# EFR32BG24_PartC.net
KiCad netlist of a schematic drawn in Altium Designer
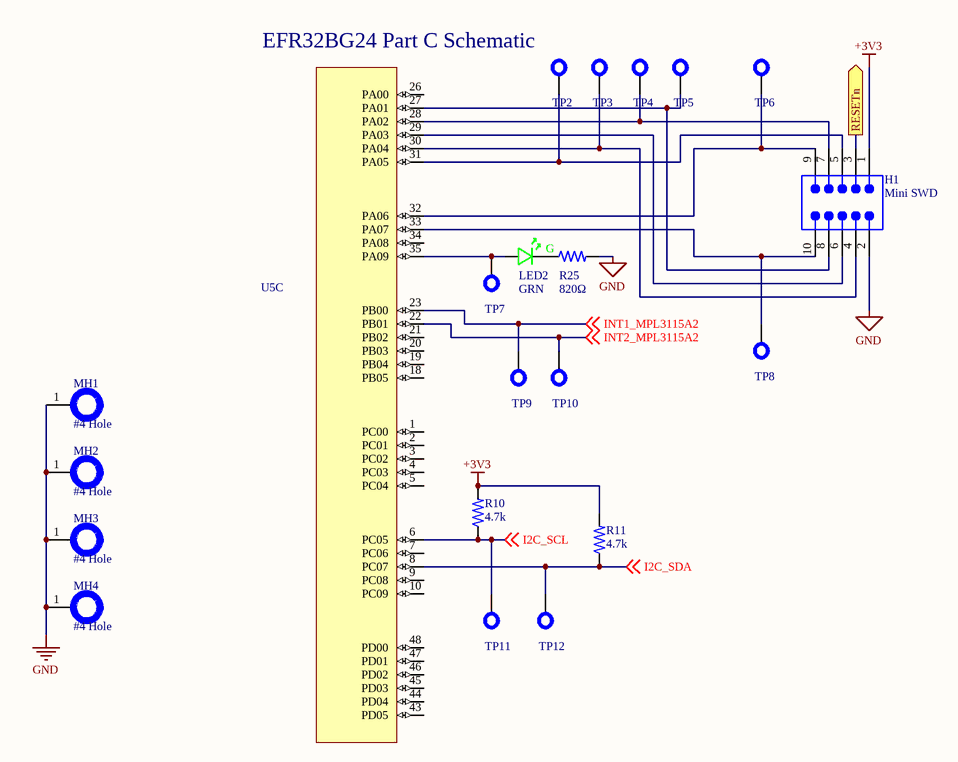
[diagram p0: EFR32BG24_PartC.SchDoc]

(export (version "E")
  (design (tool "Eeschema 10.0.6"))
  (components
    (comp (ref "H1")
      (value "Mini SWD")
      (footprint "FTSH-105-01-XXX-DV-K")
      (description "Mini SWD 0.05\" Pitch Connector - 10 Pin SMT Box Header")
      (fields
        (field (name "MANUFACTURER") "Adafruit Industries")
        (field (name "MANUFACTURER PART NUMBER") "4048")
      )
      (libsource (lib "Connectors") (part "Debug Connector Mini SWD - 0.05{dblquote}"))
    )
    (comp (ref "LED2")
      (value "GRN")
      (footprint "LED_0603")
      (description "LED, 0603, GREEN, 430MCD, 520NM")
      (fields
        (field (name "MANUFACTURER") "Wurth Electronics")
        (field (name "MANUFACTURER PART NUMBER") "150060GS75000")
      )
      (libsource (lib "LPEDT_Parts") (part "LED_GREEN_0603"))
    )
    (comp (ref "MH1")
      (value "#4 Hole")
      (footprint "HOLE_#4")
      (libsource (lib "LPEDT_Parts") (part "HOLE_#4"))
    )
    (comp (ref "MH2")
      (value "#4 Hole")
      (footprint "HOLE_#4")
      (libsource (lib "LPEDT_Parts") (part "HOLE_#4"))
    )
    (comp (ref "MH3")
      (value "#4 Hole")
      (footprint "HOLE_#4")
      (libsource (lib "LPEDT_Parts") (part "HOLE_#4"))
    )
    (comp (ref "MH4")
      (value "#4 Hole")
      (footprint "HOLE_#4")
      (libsource (lib "LPEDT_Parts") (part "HOLE_#4"))
    )
    (comp (ref "R10")
      (value "4.7k")
      (footprint "R_0603")
      (fields
        (field (name "MANUFACTURER") "Yageo")
        (field (name "MANUFACTURER PART NUMBER") "RC0603FR-074K7L")
        (field (name "TOLERANCE") "1%")
      )
      (libsource (lib "LPEDT_Parts") (part "R_4K7_0603"))
    )
    (comp (ref "R11")
      (value "4.7k")
      (footprint "R_0603")
      (fields
        (field (name "MANUFACTURER") "Yageo")
        (field (name "MANUFACTURER PART NUMBER") "RC0603FR-074K7L")
        (field (name "TOLERANCE") "1%")
      )
      (libsource (lib "LPEDT_Parts") (part "R_4K7_0603"))
    )
    (comp (ref "R25")
      (value "820Ω")
      (footprint "R_0603")
      (description "RES 820OHM 0.1W 0603")
      (fields
        (field (name "MANUFACTURER") "Stackpole Electronics")
        (field (name "MANUFACTURER PART NUMBER") "RMCF0603FT820R")
      )
      (libsource (lib "LPEDT_Parts") (part "R_820_0603"))
    )
    (comp (ref "TP2")
      (value "TP_1PIN_Hole")
      (footprint "Test Point")
      (description "200 mil hole test point")
      (libsource (lib "LPEDT_Parts") (part "TP_1PIN_Hole"))
    )
    (comp (ref "TP3")
      (value "TP_1PIN_Hole")
      (footprint "Test Point")
      (description "200 mil hole test point")
      (libsource (lib "LPEDT_Parts") (part "TP_1PIN_Hole"))
    )
    (comp (ref "TP4")
      (value "TP_1PIN_Hole")
      (footprint "Test Point")
      (description "200 mil hole test point")
      (libsource (lib "LPEDT_Parts") (part "TP_1PIN_Hole"))
    )
    (comp (ref "TP5")
      (value "TP_1PIN_Hole")
      (footprint "Test Point")
      (description "200 mil hole test point")
      (libsource (lib "LPEDT_Parts") (part "TP_1PIN_Hole"))
    )
    (comp (ref "TP6")
      (value "TP_1PIN_Hole")
      (footprint "Test Point")
      (description "200 mil hole test point")
      (libsource (lib "LPEDT_Parts") (part "TP_1PIN_Hole"))
    )
    (comp (ref "TP7")
      (value "TP_1PIN_Hole")
      (footprint "Test Point")
      (description "200 mil hole test point")
      (libsource (lib "LPEDT_Parts") (part "TP_1PIN_Hole"))
    )
    (comp (ref "TP8")
      (value "TP_1PIN_Hole")
      (footprint "Test Point")
      (description "200 mil hole test point")
      (libsource (lib "LPEDT_Parts") (part "TP_1PIN_Hole"))
    )
    (comp (ref "TP9")
      (value "TP_1PIN_Hole")
      (footprint "Test Point")
      (description "200 mil hole test point")
      (libsource (lib "LPEDT_Parts") (part "TP_1PIN_Hole"))
    )
    (comp (ref "TP10")
      (value "TP_1PIN_Hole")
      (footprint "Test Point")
      (description "200 mil hole test point")
      (libsource (lib "LPEDT_Parts") (part "TP_1PIN_Hole"))
    )
    (comp (ref "TP11")
      (value "TP_1PIN_Hole")
      (footprint "Test Point")
      (description "200 mil hole test point")
      (libsource (lib "LPEDT_Parts") (part "TP_1PIN_Hole"))
    )
    (comp (ref "TP12")
      (value "TP_1PIN_Hole")
      (footprint "Test Point")
      (description "200 mil hole test point")
      (libsource (lib "LPEDT_Parts") (part "TP_1PIN_Hole"))
    )
    (comp (ref "U5")
      (value "EFR32BG24B110F1536IM48-B")
      (footprint "U_48QFN_6x6_2")
      (description "BG24, 2.4 GHz, 1536kB Flash, 256kB RAM, +10 dBm, Secure Vault High, 20-bit ADC +125C, QFN48")
      (fields (field (name "MANUFACTURER") "Silicon Labs"))
      (libsource (lib "LPEDT_Parts") (part "EFR32BG24B110F1536IM48-B"))
    )
  )
  (nets
    (net (code "1") (name "+3V3") (class "Default")
      (node (ref "H1") (pin "1") (pinfunction "1_1") (pintype "passive"))
      (node (ref "R10") (pin "2") (pinfunction "2_2") (pintype "passive"))
      (node (ref "R11") (pin "2") (pinfunction "2_2") (pintype "passive"))
    )
    (net (code "2") (name "/RESETn") (class "Default")
      (node (ref "H1") (pin "3") (pinfunction "3_3") (pintype "passive"))
    )
    (net (code "3") (name "GND") (class "Default")
      (node (ref "H1") (pin "2") (pinfunction "2_2") (pintype "passive"))
      (node (ref "MH1") (pin "1") (pinfunction "1_1") (pintype "passive"))
      (node (ref "MH2") (pin "1") (pinfunction "1_1") (pintype "passive"))
      (node (ref "MH3") (pin "1") (pinfunction "1_1") (pintype "passive"))
      (node (ref "MH4") (pin "1") (pinfunction "1_1") (pintype "passive"))
      (node (ref "R25") (pin "2") (pinfunction "2_2") (pintype "passive"))
    )
    (net (code "4") (name "I2C_SCL") (class "Default")
      (node (ref "R10") (pin "1") (pinfunction "1_1") (pintype "passive"))
      (node (ref "TP11") (pin "1") (pinfunction "1_1") (pintype "passive"))
      (node (ref "U5") (pin "6") (pinfunction "PC05_6") (pintype "bidirectional"))
    )
    (net (code "5") (name "I2C_SDA") (class "Default")
      (node (ref "R11") (pin "1") (pinfunction "1_1") (pintype "passive"))
      (node (ref "TP12") (pin "1") (pinfunction "1_1") (pintype "passive"))
      (node (ref "U5") (pin "8") (pinfunction "PC07_8") (pintype "bidirectional"))
    )
    (net (code "6") (name "INT1_MPL3115A2") (class "Default")
      (node (ref "TP9") (pin "1") (pinfunction "1_1") (pintype "passive"))
      (node (ref "U5") (pin "23") (pinfunction "PB00_23") (pintype "bidirectional"))
    )
    (net (code "7") (name "INT2_MPL3115A2") (class "Default")
      (node (ref "TP10") (pin "1") (pinfunction "1_1") (pintype "passive"))
      (node (ref "U5") (pin "22") (pinfunction "PB01_22") (pintype "bidirectional"))
    )
    (net (code "8") (name "Net-(LED2-PadC)") (class "Default")
      (node (ref "LED2") (pin "C") (pinfunction "C_C") (pintype "passive"))
      (node (ref "R25") (pin "1") (pinfunction "1_1") (pintype "passive"))
    )
    (net (code "9") (name "Net-(U5C-PA01)") (class "Default")
      (node (ref "H1") (pin "8") (pinfunction "8_8") (pintype "passive"))
      (node (ref "TP5") (pin "1") (pinfunction "1_1") (pintype "passive"))
      (node (ref "U5") (pin "27") (pinfunction "PA01_27") (pintype "bidirectional"))
    )
    (net (code "10") (name "Net-(U5C-PA02)") (class "Default")
      (node (ref "H1") (pin "7") (pinfunction "7_7") (pintype "passive"))
      (node (ref "TP4") (pin "1") (pinfunction "1_1") (pintype "passive"))
      (node (ref "U5") (pin "28") (pinfunction "PA02_28") (pintype "bidirectional"))
    )
    (net (code "11") (name "Net-(U5C-PA03)") (class "Default")
      (node (ref "H1") (pin "6") (pinfunction "6_6") (pintype "passive"))
      (node (ref "U5") (pin "29") (pinfunction "PA03_29") (pintype "bidirectional"))
    )
    (net (code "12") (name "Net-(U5C-PA04)") (class "Default")
      (node (ref "H1") (pin "4") (pinfunction "4_4") (pintype "passive"))
      (node (ref "TP3") (pin "1") (pinfunction "1_1") (pintype "passive"))
      (node (ref "U5") (pin "30") (pinfunction "PA04_30") (pintype "bidirectional"))
    )
    (net (code "13") (name "Net-(U5C-PA05)") (class "Default")
      (node (ref "H1") (pin "5") (pinfunction "5_5") (pintype "passive"))
      (node (ref "TP2") (pin "1") (pinfunction "1_1") (pintype "passive"))
      (node (ref "U5") (pin "31") (pinfunction "PA05_31") (pintype "bidirectional"))
    )
    (net (code "14") (name "Net-(U5C-PA06)") (class "Default")
      (node (ref "H1") (pin "9") (pinfunction "9_9") (pintype "passive"))
      (node (ref "TP6") (pin "1") (pinfunction "1_1") (pintype "passive"))
      (node (ref "U5") (pin "32") (pinfunction "PA06_32") (pintype "bidirectional"))
    )
    (net (code "15") (name "Net-(U5C-PA07)") (class "Default")
      (node (ref "H1") (pin "10") (pinfunction "10_10") (pintype "passive"))
      (node (ref "TP8") (pin "1") (pinfunction "1_1") (pintype "passive"))
      (node (ref "U5") (pin "33") (pinfunction "PA07_33") (pintype "bidirectional"))
    )
    (net (code "16") (name "Net-(U5C-PA09)") (class "Default")
      (node (ref "LED2") (pin "A") (pinfunction "A_A") (pintype "passive"))
      (node (ref "TP7") (pin "1") (pinfunction "1_1") (pintype "passive"))
      (node (ref "U5") (pin "35") (pinfunction "PA09_35") (pintype "bidirectional"))
    )
    (net (code "17") (name "unconnected-(U5C-PA00-Pad26)") (class "Default")
      (node (ref "U5") (pin "26") (pinfunction "PA00_26") (pintype "bidirectional"))
    )
    (net (code "18") (name "unconnected-(U5C-PA08-Pad34)") (class "Default")
      (node (ref "U5") (pin "34") (pinfunction "PA08_34") (pintype "bidirectional"))
    )
    (net (code "19") (name "unconnected-(U5C-PB02-Pad21)") (class "Default")
      (node (ref "U5") (pin "21") (pinfunction "PB02_21") (pintype "bidirectional"))
    )
    (net (code "20") (name "unconnected-(U5C-PB03-Pad20)") (class "Default")
      (node (ref "U5") (pin "20") (pinfunction "PB03_20") (pintype "bidirectional"))
    )
    (net (code "21") (name "unconnected-(U5C-PB04-Pad19)") (class "Default")
      (node (ref "U5") (pin "19") (pinfunction "PB04_19") (pintype "bidirectional"))
    )
    (net (code "22") (name "unconnected-(U5C-PB05-Pad18)") (class "Default")
      (node (ref "U5") (pin "18") (pinfunction "PB05_18") (pintype "bidirectional"))
    )
    (net (code "23") (name "unconnected-(U5C-PC00-Pad1)") (class "Default")
      (node (ref "U5") (pin "1") (pinfunction "PC00_1") (pintype "bidirectional"))
    )
    (net (code "24") (name "unconnected-(U5C-PC01-Pad2)") (class "Default")
      (node (ref "U5") (pin "2") (pinfunction "PC01_2") (pintype "bidirectional"))
    )
    (net (code "25") (name "unconnected-(U5C-PC02-Pad3)") (class "Default")
      (node (ref "U5") (pin "3") (pinfunction "PC02_3") (pintype "bidirectional"))
    )
    (net (code "26") (name "unconnected-(U5C-PC03-Pad4)") (class "Default")
      (node (ref "U5") (pin "4") (pinfunction "PC03_4") (pintype "bidirectional"))
    )
    (net (code "27") (name "unconnected-(U5C-PC04-Pad5)") (class "Default")
      (node (ref "U5") (pin "5") (pinfunction "PC04_5") (pintype "bidirectional"))
    )
    (net (code "28") (name "unconnected-(U5C-PC06-Pad7)") (class "Default")
      (node (ref "U5") (pin "7") (pinfunction "PC06_7") (pintype "bidirectional"))
    )
    (net (code "29") (name "unconnected-(U5C-PC08-Pad9)") (class "Default")
      (node (ref "U5") (pin "9") (pinfunction "PC08_9") (pintype "bidirectional"))
    )
    (net (code "30") (name "unconnected-(U5C-PC09-Pad10)") (class "Default")
      (node (ref "U5") (pin "10") (pinfunction "PC09_10") (pintype "bidirectional"))
    )
    (net (code "31") (name "unconnected-(U5C-PD00-Pad48)") (class "Default")
      (node (ref "U5") (pin "48") (pinfunction "PD00_48") (pintype "bidirectional"))
    )
    (net (code "32") (name "unconnected-(U5C-PD01-Pad47)") (class "Default")
      (node (ref "U5") (pin "47") (pinfunction "PD01_47") (pintype "bidirectional"))
    )
    (net (code "33") (name "unconnected-(U5C-PD02-Pad46)") (class "Default")
      (node (ref "U5") (pin "46") (pinfunction "PD02_46") (pintype "bidirectional"))
    )
    (net (code "34") (name "unconnected-(U5C-PD03-Pad45)") (class "Default")
      (node (ref "U5") (pin "45") (pinfunction "PD03_45") (pintype "bidirectional"))
    )
    (net (code "35") (name "unconnected-(U5C-PD04-Pad44)") (class "Default")
      (node (ref "U5") (pin "44") (pinfunction "PD04_44") (pintype "bidirectional"))
    )
    (net (code "36") (name "unconnected-(U5C-PD05-Pad43)") (class "Default")
      (node (ref "U5") (pin "43") (pinfunction "PD05_43") (pintype "bidirectional"))
    )
  )
)
